# power_shield_v1.net
KiCad netlist of a schematic drawn in EAGLE
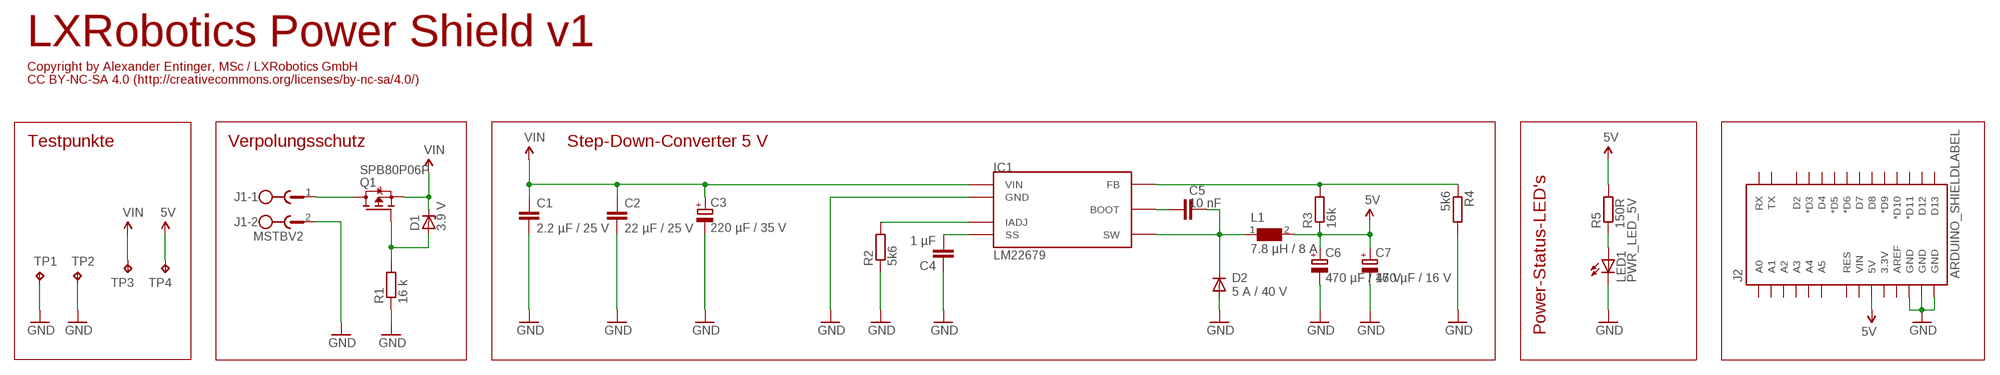
[diagram p0: schematic, sheet 1]

(export (version "E")
  (design (tool "Eeschema 10.0.6"))
  (components
    (comp (ref "C1")
      (value "2.2 µF / 25 V")
      (footprint "eagle-import:C1206")
      (libsource (lib "eagle-import") (part "C-EUC1206"))
    )
    (comp (ref "C2")
      (value "22 µF / 25 V")
      (footprint "eagle-import:C1210")
      (libsource (lib "eagle-import") (part "C-EUC1210"))
    )
    (comp (ref "C3")
      (value "220 µF / 35 V")
      (footprint "eagle-import:PANASONIC_F")
      (libsource (lib "eagle-import") (part "CPOL-EUF"))
    )
    (comp (ref "C4")
      (value "1 µF")
      (footprint "eagle-import:C0805")
      (libsource (lib "eagle-import") (part "C-EUC0805"))
    )
    (comp (ref "C5")
      (value "10 nF")
      (footprint "eagle-import:C0805")
      (libsource (lib "eagle-import") (part "C-EUC0805"))
    )
    (comp (ref "C6")
      (value "470 µF / 16 V")
      (footprint "eagle-import:PANASONIC_F")
      (libsource (lib "eagle-import") (part "CPOL-EUF"))
    )
    (comp (ref "C7")
      (value "470 µF / 16 V")
      (footprint "eagle-import:PANASONIC_F")
      (libsource (lib "eagle-import") (part "CPOL-EUF"))
    )
    (comp (ref "D1")
      (value "3.9 V")
      (footprint "eagle-import:SMB")
      (libsource (lib "eagle-import") (part "ZENER-DIODESMB"))
    )
    (comp (ref "D2")
      (value "5 A / 40 V")
      (footprint "eagle-import:SMC")
      (libsource (lib "eagle-import") (part "DIODE-SMC"))
    )
    (comp (ref "IC1")
      (value "LM22679")
      (footprint "eagle-import:P-TO263-7-1")
      (libsource (lib "eagle-import") (part "LM22679"))
    )
    (comp (ref "J1")
      (value "MSTBV2")
      (footprint "eagle-import:MSTBV2")
      (fields (field (name "MPN") "MSTBV 2,5/2-GF-5.08"))
      (libsource (lib "eagle-import") (part "MSTBV2"))
    )
    (comp (ref "J2")
      (value "ARDUINO_SHIELDLABEL")
      (footprint "eagle-import:DUEMILANOVE_SHIELD")
      (libsource (lib "eagle-import") (part "ARDUINO_SHIELDLABEL"))
    )
    (comp (ref "L1")
      (value "7.8 µH / 8 A")
      (footprint "eagle-import:WE-HCI_1050")
      (fields (field (name "MPN") "744325780"))
      (libsource (lib "eagle-import") (part "WE-HCI_1050-744325780"))
    )
    (comp (ref "LED1")
      (value "PWR_LED_5V")
      (footprint "eagle-import:CHIPLED_0805")
      (libsource (lib "eagle-import") (part "LEDCHIPLED_0805"))
    )
    (comp (ref "Q1")
      (value "SPB80P06P")
      (footprint "eagle-import:TO263")
      (libsource (lib "eagle-import") (part "SPB80P06P"))
    )
    (comp (ref "R1")
      (value "16 k")
      (footprint "eagle-import:M0805")
      (libsource (lib "eagle-import") (part "R-EU_M0805"))
    )
    (comp (ref "R2")
      (value "5k6")
      (footprint "eagle-import:M0805")
      (libsource (lib "eagle-import") (part "R-EU_M0805"))
    )
    (comp (ref "R3")
      (value "16k")
      (footprint "eagle-import:M0805")
      (libsource (lib "eagle-import") (part "R-EU_M0805"))
    )
    (comp (ref "R4")
      (value "5k6")
      (footprint "eagle-import:M0805")
      (libsource (lib "eagle-import") (part "R-EU_M0805"))
    )
    (comp (ref "R5")
      (value "150R")
      (footprint "eagle-import:M0805")
      (libsource (lib "eagle-import") (part "R-EU_M0805"))
    )
    (comp (ref "TP1")
      (value "TPB1,27")
      (footprint "eagle-import:B1,27")
      (libsource (lib "eagle-import") (part "TPB1,27"))
    )
    (comp (ref "TP2")
      (value "TPB1,27")
      (footprint "eagle-import:B1,27")
      (libsource (lib "eagle-import") (part "TPB1,27"))
    )
    (comp (ref "TP3")
      (value "TPB1,27")
      (footprint "eagle-import:B1,27")
      (libsource (lib "eagle-import") (part "TPB1,27"))
    )
    (comp (ref "TP4")
      (value "TPB1,27")
      (footprint "eagle-import:B1,27")
      (libsource (lib "eagle-import") (part "TPB1,27"))
    )
  )
  (nets
    (net (code "1") (name "5V") (class "Default")
      (node (ref "C6") (pin "+") (pinfunction "+_+") (pintype "passive"))
      (node (ref "C7") (pin "+") (pinfunction "+_+") (pintype "passive"))
      (node (ref "J2") (pin "5V") (pinfunction "5V_5V") (pintype "bidirectional"))
      (node (ref "L1") (pin "2") (pinfunction "2_2") (pintype "passive"))
      (node (ref "R3") (pin "1") (pinfunction "1_1") (pintype "passive"))
      (node (ref "R5") (pin "2") (pinfunction "2_2") (pintype "passive"))
      (node (ref "TP4") (pin "TP") (pinfunction "TP_TP") (pintype "input"))
    )
    (net (code "2") (name "GND") (class "Default")
      (node (ref "C1") (pin "2") (pinfunction "2_2") (pintype "passive"))
      (node (ref "C2") (pin "2") (pinfunction "2_2") (pintype "passive"))
      (node (ref "C3") (pin "-") (pinfunction "-_-") (pintype "passive"))
      (node (ref "C4") (pin "1") (pinfunction "1_1") (pintype "passive"))
      (node (ref "C6") (pin "-") (pinfunction "-_-") (pintype "passive"))
      (node (ref "C7") (pin "-") (pinfunction "-_-") (pintype "passive"))
      (node (ref "D2") (pin "A") (pinfunction "A_A") (pintype "passive"))
      (node (ref "IC1") (pin "4") (pinfunction "GND_4") (pintype "bidirectional"))
      (node (ref "IC1") (pin "TH") (pinfunction "GND_TH") (pintype "bidirectional"))
      (node (ref "J1") (pin "2") (pinfunction "1_2") (pintype "passive"))
      (node (ref "J2") (pin "GND@0") (pinfunction "GND_GND@0") (pintype "bidirectional"))
      (node (ref "J2") (pin "GND@1") (pinfunction "GND_GND@1") (pintype "bidirectional"))
      (node (ref "J2") (pin "GND@2") (pinfunction "GND_GND@2") (pintype "bidirectional"))
      (node (ref "LED1") (pin "C") (pinfunction "C_C") (pintype "passive"))
      (node (ref "R1") (pin "1") (pinfunction "1_1") (pintype "passive"))
      (node (ref "R2") (pin "1") (pinfunction "1_1") (pintype "passive"))
      (node (ref "R4") (pin "2") (pinfunction "2_2") (pintype "passive"))
      (node (ref "TP1") (pin "TP") (pinfunction "TP_TP") (pintype "input"))
      (node (ref "TP2") (pin "TP") (pinfunction "TP_TP") (pintype "input"))
    )
    (net (code "3") (name "Net-(IC1-BOOT)") (class "Default")
      (node (ref "C5") (pin "1") (pinfunction "1_1") (pintype "passive"))
      (node (ref "IC1") (pin "3") (pinfunction "BOOT_3") (pintype "bidirectional"))
    )
    (net (code "4") (name "Net-(IC1-FB)") (class "Default")
      (node (ref "IC1") (pin "6") (pinfunction "FB_6") (pintype "bidirectional"))
      (node (ref "R3") (pin "2") (pinfunction "2_2") (pintype "passive"))
      (node (ref "R4") (pin "1") (pinfunction "1_1") (pintype "passive"))
    )
    (net (code "5") (name "Net-(IC1-IADJ)") (class "Default")
      (node (ref "IC1") (pin "5") (pinfunction "IADJ_5") (pintype "bidirectional"))
      (node (ref "R2") (pin "2") (pinfunction "2_2") (pintype "passive"))
    )
    (net (code "6") (name "Net-(IC1-SS)") (class "Default")
      (node (ref "C4") (pin "2") (pinfunction "2_2") (pintype "passive"))
      (node (ref "IC1") (pin "7") (pinfunction "SS_7") (pintype "bidirectional"))
    )
    (net (code "7") (name "Net-(IC1-SW)") (class "Default")
      (node (ref "C5") (pin "2") (pinfunction "2_2") (pintype "passive"))
      (node (ref "D2") (pin "C") (pinfunction "C_C") (pintype "passive"))
      (node (ref "IC1") (pin "1") (pinfunction "SW_1") (pintype "bidirectional"))
      (node (ref "L1") (pin "1") (pinfunction "1_1") (pintype "passive"))
    )
    (net (code "8") (name "Net-(LED1-PadA)") (class "Default")
      (node (ref "LED1") (pin "A") (pinfunction "A_A") (pintype "passive"))
      (node (ref "R5") (pin "1") (pinfunction "1_1") (pintype "passive"))
    )
    (net (code "9") (name "Net-(Q1-D)") (class "Default")
      (node (ref "J1") (pin "1") (pinfunction "1_1") (pintype "passive"))
      (node (ref "Q1") (pin "3") (pinfunction "D_3") (pintype "passive"))
    )
    (net (code "10") (name "Net-(Q1-G)") (class "Default")
      (node (ref "D1") (pin "A") (pinfunction "A_A") (pintype "passive"))
      (node (ref "Q1") (pin "1") (pinfunction "G_1") (pintype "passive"))
      (node (ref "R1") (pin "2") (pinfunction "2_2") (pintype "passive"))
    )
    (net (code "11") (name "VIN") (class "Default")
      (node (ref "C1") (pin "1") (pinfunction "1_1") (pintype "passive"))
      (node (ref "C2") (pin "1") (pinfunction "1_1") (pintype "passive"))
      (node (ref "C3") (pin "+") (pinfunction "+_+") (pintype "passive"))
      (node (ref "D1") (pin "C") (pinfunction "C_C") (pintype "passive"))
      (node (ref "IC1") (pin "2") (pinfunction "VIN_2") (pintype "bidirectional"))
      (node (ref "Q1") (pin "2") (pinfunction "S_2") (pintype "passive"))
      (node (ref "TP3") (pin "TP") (pinfunction "TP_TP") (pintype "input"))
    )
    (net (code "12") (name "unconnected-(J2-*D3-PadD3)") (class "Default")
      (node (ref "J2") (pin "D3") (pinfunction "*D3_D3") (pintype "bidirectional"))
    )
    (net (code "13") (name "unconnected-(J2-*D5-PadD5)") (class "Default")
      (node (ref "J2") (pin "D5") (pinfunction "*D5_D5") (pintype "bidirectional"))
    )
    (net (code "14") (name "unconnected-(J2-*D6-PadD6)") (class "Default")
      (node (ref "J2") (pin "D6") (pinfunction "*D6_D6") (pintype "bidirectional"))
    )
    (net (code "15") (name "unconnected-(J2-*D9-PadD9)") (class "Default")
      (node (ref "J2") (pin "D9") (pinfunction "*D9_D9") (pintype "bidirectional"))
    )
    (net (code "16") (name "unconnected-(J2-*D10-PadD10)") (class "Default")
      (node (ref "J2") (pin "D10") (pinfunction "*D10_D10") (pintype "bidirectional"))
    )
    (net (code "17") (name "unconnected-(J2-*D11-PadD11)") (class "Default")
      (node (ref "J2") (pin "D11") (pinfunction "*D11_D11") (pintype "bidirectional"))
    )
    (net (code "18") (name "unconnected-(J2-Pad3.3V)") (class "Default")
      (node (ref "J2") (pin "3.3V") (pinfunction "3.3V_3.3V") (pintype "bidirectional"))
    )
    (net (code "19") (name "unconnected-(J2-PadA0)") (class "Default")
      (node (ref "J2") (pin "A0") (pinfunction "A0_A0") (pintype "bidirectional"))
    )
    (net (code "20") (name "unconnected-(J2-PadA1)") (class "Default")
      (node (ref "J2") (pin "A1") (pinfunction "A1_A1") (pintype "bidirectional"))
    )
    (net (code "21") (name "unconnected-(J2-PadA2)") (class "Default")
      (node (ref "J2") (pin "A2") (pinfunction "A2_A2") (pintype "bidirectional"))
    )
    (net (code "22") (name "unconnected-(J2-PadA3)") (class "Default")
      (node (ref "J2") (pin "A3") (pinfunction "A3_A3") (pintype "bidirectional"))
    )
    (net (code "23") (name "unconnected-(J2-PadA4)") (class "Default")
      (node (ref "J2") (pin "A4") (pinfunction "A4_A4") (pintype "bidirectional"))
    )
    (net (code "24") (name "unconnected-(J2-PadA5)") (class "Default")
      (node (ref "J2") (pin "A5") (pinfunction "A5_A5") (pintype "bidirectional"))
    )
    (net (code "25") (name "unconnected-(J2-PadAREF)") (class "Default")
      (node (ref "J2") (pin "AREF") (pinfunction "AREF_AREF") (pintype "bidirectional"))
    )
    (net (code "26") (name "unconnected-(J2-PadD2)") (class "Default")
      (node (ref "J2") (pin "D2") (pinfunction "D2_D2") (pintype "bidirectional"))
    )
    (net (code "27") (name "unconnected-(J2-PadD4)") (class "Default")
      (node (ref "J2") (pin "D4") (pinfunction "D4_D4") (pintype "bidirectional"))
    )
    (net (code "28") (name "unconnected-(J2-PadD7)") (class "Default")
      (node (ref "J2") (pin "D7") (pinfunction "D7_D7") (pintype "bidirectional"))
    )
    (net (code "29") (name "unconnected-(J2-PadD8)") (class "Default")
      (node (ref "J2") (pin "D8") (pinfunction "D8_D8") (pintype "bidirectional"))
    )
    (net (code "30") (name "unconnected-(J2-PadD12)") (class "Default")
      (node (ref "J2") (pin "D12") (pinfunction "D12_D12") (pintype "bidirectional"))
    )
    (net (code "31") (name "unconnected-(J2-PadD13)") (class "Default")
      (node (ref "J2") (pin "D13") (pinfunction "D13_D13") (pintype "bidirectional"))
    )
    (net (code "32") (name "unconnected-(J2-PadRES)") (class "Default")
      (node (ref "J2") (pin "RES") (pinfunction "RES_RES") (pintype "bidirectional"))
    )
    (net (code "33") (name "unconnected-(J2-PadRX)") (class "Default")
      (node (ref "J2") (pin "RX") (pinfunction "RX_RX") (pintype "bidirectional"))
    )
    (net (code "34") (name "unconnected-(J2-PadTX)") (class "Default")
      (node (ref "J2") (pin "TX") (pinfunction "TX_TX") (pintype "bidirectional"))
    )
    (net (code "35") (name "unconnected-(J2-PadVIN)") (class "Default")
      (node (ref "J2") (pin "VIN") (pinfunction "VIN_VIN") (pintype "bidirectional"))
    )
  )
)
